# Sheet1.net
KiCad netlist of a schematic drawn in Altium Designer
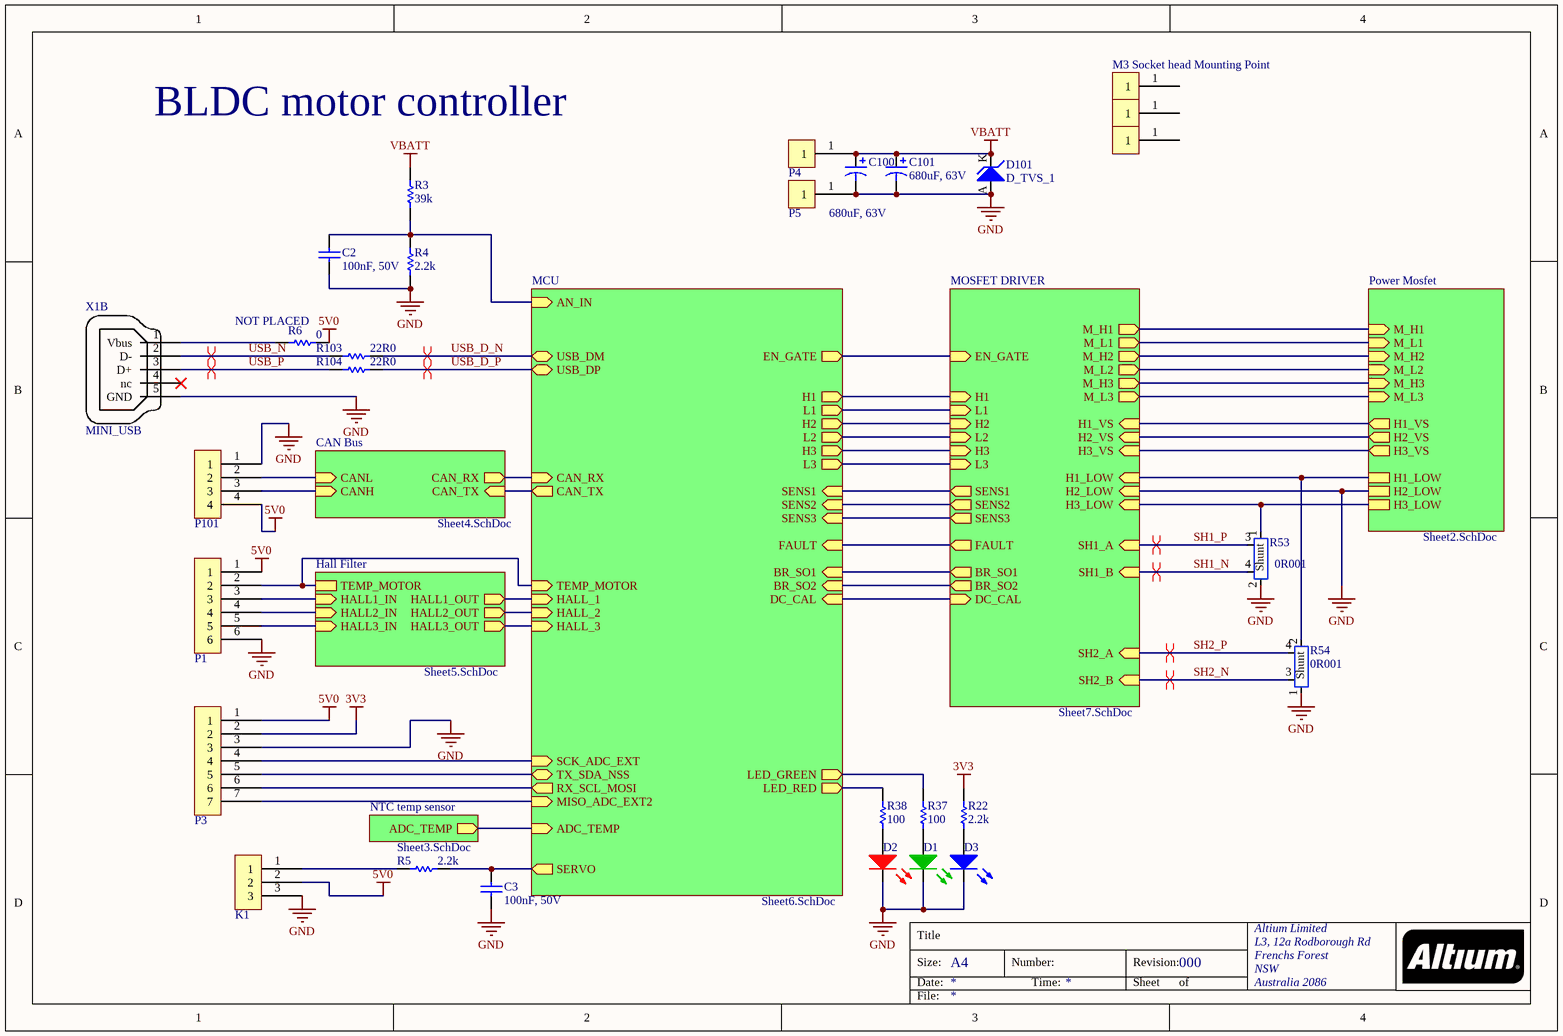
[diagram p0: Sheet1.SchDoc]

(export (version "E")
  (design (tool "Eeschema 10.0.6"))
  (components
    (comp (ref "C2")
      (value "100nF, 50V")
      (footprint "SMD-0603 Capacitor")
      (description "CAP 100n, 50V, 0603")
      (fields
        (field (name "MANUFACTURER PART NUMBER") "06035C104JAT2A")
        (field (name "MANUFACTURER") "AVX Corporation")
      )
      (libsource (lib "Master Data Link") (part "CAP"))
    )
    (comp (ref "C3")
      (value "100nF, 50V")
      (footprint "SMD-0603 Capacitor")
      (description "CAP 100n, 50V, 0603")
      (fields
        (field (name "MANUFACTURER PART NUMBER") "06035C104JAT2A")
        (field (name "MANUFACTURER") "AVX Corporation")
      )
      (libsource (lib "Master Data Link") (part "CAP"))
    )
    (comp (ref "C100")
      (value "680uF, 63V")
      (footprint "ALU CAP 16DIA 25HIGH")
      (description "680µF 63V Aluminum Capacitors Radial")
      (fields
        (field (name "MANUFACTURER PART NUMBER") "UPW1J681MHD")
        (field (name "MANUFACTURER") "Nichicon")
      )
      (libsource (lib "Master Data Link") (part "CAP_POL"))
    )
    (comp (ref "C101")
      (value "680uF, 63V")
      (footprint "ALU CAP 16DIA 25HIGH")
      (description "680µF 63V Aluminum Capacitors Radial")
      (fields
        (field (name "MANUFACTURER PART NUMBER") "UPW1J681MHD")
        (field (name "MANUFACTURER") "Nichicon")
      )
      (libsource (lib "Master Data Link") (part "CAP_POL"))
    )
    (comp (ref "D1")
      (value "LED_GREEN")
      (footprint "SMD-0603 LED GREEN")
      (description "LED Green, 0603")
      (fields (field (name "PART NUMBER") "LTST-C191KGKT") (field (name "MANUFACTURER") "Lite-On Inc."))
      (libsource (lib "Master Data Link") (part "LED_GREEN"))
    )
    (comp (ref "D2")
      (value "LED_RED")
      (footprint "SMD-0603 LED RED")
      (description "LED Red, 0603")
      (fields (field (name "PART NUMBER") "LTST-C191KRKT") (field (name "MANUFACTURER") "Lite-On Inc."))
      (libsource (lib "Master Data Link") (part "LED_RED"))
    )
    (comp (ref "D3")
      (value "LED_BLUE")
      (footprint "SMD-0603 LED BLUE")
      (description "LED Blue, 0603")
      (fields (field (name "PART NUMBER") "LBQ39GN1P1351") (field (name "MANUFACTURER") "OSRAM"))
      (libsource (lib "Master Data Link") (part "LED_BLUE"))
    )
    (comp (ref "D101")
      (value "D_TVS_1")
      (footprint "SMC-403-03")
      (description "TVS DIODE 51VWM 82.4VC SMC")
      (fields
        (field (name "MANUFACTURER PART NUMBER") "SMCJ51A")
        (field (name "MANUFACTURER") "ON Semiconductor")
      )
      (libsource (lib "Master Data Link") (part "D_TVS_1"))
    )
    (comp (ref "K1")
      (value "-")
      (footprint "HEADER 3 PIN")
      (description "Breakaway 3 pin Through hole")
      (libsource (lib "Master Data Link") (part "CON3"))
    )
    (comp (ref "M1")
      (value "M3 Socket head Mounting Point")
      (footprint "M3 Socket head")
      (libsource (lib "Master Data Link") (part "CON1"))
    )
    (comp (ref "M2")
      (value "M3 Socket head Mounting Point")
      (footprint "M3 Socket head")
      (libsource (lib "Master Data Link") (part "CON1"))
    )
    (comp (ref "M3")
      (value "M3 Socket head Mounting Point")
      (footprint "M3 Socket head")
      (libsource (lib "Master Data Link") (part "CON1"))
    )
    (comp (ref "P1")
      (value "B6B-PH-K-S(LF)(SN)")
      (footprint "JST PH TH VERT 6")
      (description "JST PH Through hole Vertical 6 Pin")
      (fields (field (name "MANUFACTURER") "JST"))
      (libsource (lib "Master Data Link") (part "CON6"))
    )
    (comp (ref "P3")
      (value "B7B-PH-K-S(LF)(SN)")
      (footprint "JST PH TH VERT 7")
      (description "JST PH Through hole Vertical 7 Pin")
      (fields (field (name "MANUFACTURER") "JST"))
      (libsource (lib "Master Data Link") (part "CON7"))
    )
    (comp (ref "P4")
      (value "-")
      (footprint "PAD1")
      (description "SMD Power landing")
      (libsource (lib "Master Data Link") (part "CON1"))
    )
    (comp (ref "P5")
      (value "-")
      (footprint "PAD1")
      (description "SMD Power landing")
      (libsource (lib "Master Data Link") (part "CON1"))
    )
    (comp (ref "P101")
      (value "B4B-PH-K-S(LF)(SN)")
      (footprint "JST PH TH VERT 4")
      (description "JST PH Through hole Vertical 4 Pin")
      (fields (field (name "MANUFACTURER") "JST"))
      (libsource (lib "Master Data Link") (part "CON4"))
    )
    (comp (ref "R3")
      (value "39k")
      (footprint "SMD-0603 Resistor")
      (description "R 39k, 0603")
      (fields
        (field (name "MANUFACTURER PART NUMBER") "ERJ-3EKF3902V")
        (field (name "MANUFACTURER") "Panasonic Electronic Components")
      )
      (libsource (lib "Master Data Link") (part "RES"))
    )
    (comp (ref "R4")
      (value "2.2k")
      (footprint "SMD-0603 Resistor")
      (description "R 2.2k, 0603")
      (fields
        (field (name "MANUFACTURER PART NUMBER") "RK73H1JTTD2201F")
        (field (name "MANUFACTURER") "KOA Speer")
      )
      (libsource (lib "Master Data Link") (part "RES"))
    )
    (comp (ref "R5")
      (value "2.2k")
      (footprint "SMD-0603 Resistor")
      (description "R 2.2k, 0603")
      (fields
        (field (name "MANUFACTURER PART NUMBER") "RK73H1JTTD2201F")
        (field (name "MANUFACTURER") "KOA Speer")
      )
      (libsource (lib "Master Data Link") (part "RES"))
    )
    (comp (ref "R6")
      (value "0")
      (footprint "SMD-0603 Resistor")
      (description "R 0 ohm, 0603")
      (fields (field (name "PLACE (YES/NO)") "NOT PLACED") (field (name "MANUFACTURER") "KOA Speer"))
      (libsource (lib "Master Data Link") (part "RES"))
    )
    (comp (ref "R22")
      (value "2.2k")
      (footprint "SMD-0603 Resistor")
      (description "R 2.2k, 0603")
      (fields
        (field (name "MANUFACTURER PART NUMBER") "RK73H1JTTD2201F")
        (field (name "MANUFACTURER") "KOA Speer")
      )
      (libsource (lib "Master Data Link") (part "RES"))
    )
    (comp (ref "R37")
      (value "100")
      (footprint "SMD-0603 Resistor")
      (description "R 100ohm, 0603")
      (fields
        (field (name "MANUFACTURER PART NUMBER") "RK73H1JTTD1000F")
        (field (name "MANUFACTURER") "KOA Speer")
      )
      (libsource (lib "Master Data Link") (part "RES"))
    )
    (comp (ref "R38")
      (value "100")
      (footprint "SMD-0603 Resistor")
      (description "R 100ohm, 0603")
      (fields
        (field (name "MANUFACTURER PART NUMBER") "RK73H1JTTD1000F")
        (field (name "MANUFACTURER") "KOA Speer")
      )
      (libsource (lib "Master Data Link") (part "RES"))
    )
    (comp (ref "R53")
      (value "0R001")
      (footprint "WSLP2726")
      (description "Shunt 1mOhm")
      (fields
        (field (name "MANUFACTURER PART NUMBER") "WSLP27261L000FEA")
        (field (name "MANUFACTURER") "Vishay Dale")
      )
      (libsource (lib "Master Data Link") (part "SHUNT_1"))
    )
    (comp (ref "R54")
      (value "0R001")
      (footprint "WSLP2726")
      (description "Shunt 1mOhm MIRROR")
      (fields
        (field (name "MANUFACTURER PART NUMBER") "WSLP27261L000FEA")
        (field (name "MANUFACTURER") "Vishay Dale")
      )
      (libsource (lib "Master Data Link") (part "SHUNT_2"))
    )
    (comp (ref "R103")
      (value "22R0")
      (footprint "SMD-0603 Resistor")
      (description "R 22R, 0603")
      (fields
        (field (name "MANUFACTURER PART NUMBER") "RK73H1JTTD22R0F")
        (field (name "MANUFACTURER") "KOA Speer")
      )
      (libsource (lib "Master Data Link") (part "RES"))
    )
    (comp (ref "R104")
      (value "22R0")
      (footprint "SMD-0603 Resistor")
      (description "R 22R, 0603")
      (fields
        (field (name "MANUFACTURER PART NUMBER") "RK73H1JTTD22R0F")
        (field (name "MANUFACTURER") "KOA Speer")
      )
      (libsource (lib "Master Data Link") (part "RES"))
    )
    (comp (ref "X1B")
      (value "MINI_USB")
      (footprint "USB-MICRO B RA SMT-TH")
      (description "CONN USB MICRO B RECPT SMT R/A TH")
      (fields
        (field (name "MANUFACTURER PART NUMBER") "10118194-0001LF")
        (field (name "MANUFACTURER") "Amphenol FCI")
      )
      (libsource (lib "Master Data Link") (part "MINI_USB"))
    )
  )
  (nets
    (net (code "2") (name "/AN_IN") (class "Default")
      (node (ref "C2") (pin "1") (pinfunction "1_1") (pintype "passive"))
      (node (ref "R3") (pin "1") (pinfunction "1_1") (pintype "passive"))
      (node (ref "R4") (pin "2") (pinfunction "2_2") (pintype "passive"))
    )
    (net (code "5") (name "/CANH") (class "Default")
      (node (ref "P101") (pin "3") (pinfunction "3_3") (pintype "passive"))
    )
    (net (code "6") (name "/CANL") (class "Default")
      (node (ref "P101") (pin "2") (pinfunction "2_2") (pintype "passive"))
    )
    (net (code "13") (name "/H1_LOW") (class "Default")
      (node (ref "R54") (pin "2") (pinfunction "1_2") (pintype "passive"))
    )
    (net (code "18") (name "/H3_LOW") (class "Default")
      (node (ref "R53") (pin "1") (pinfunction "1_1") (pintype "passive"))
    )
    (net (code "20") (name "/HALL1_IN") (class "Default")
      (node (ref "P1") (pin "3") (pinfunction "3_3") (pintype "passive"))
    )
    (net (code "22") (name "/HALL2_IN") (class "Default")
      (node (ref "P1") (pin "4") (pinfunction "4_4") (pintype "passive"))
    )
    (net (code "24") (name "/HALL3_IN") (class "Default")
      (node (ref "P1") (pin "5") (pinfunction "5_5") (pintype "passive"))
    )
    (net (code "29") (name "/LED_GREEN") (class "Default")
      (node (ref "R37") (pin "2") (pinfunction "2_2") (pintype "passive"))
    )
    (net (code "30") (name "/LED_RED") (class "Default")
      (node (ref "R38") (pin "2") (pinfunction "2_2") (pintype "passive"))
    )
    (net (code "31") (name "/MISO_ADC_EXT2") (class "Default")
      (node (ref "P3") (pin "7") (pinfunction "7_7") (pintype "passive"))
    )
    (net (code "38") (name "/RX_SCL_MOSI") (class "Default")
      (node (ref "P3") (pin "6") (pinfunction "6_6") (pintype "passive"))
    )
    (net (code "39") (name "/SCK_ADC_EXT") (class "Default")
      (node (ref "P3") (pin "4") (pinfunction "4_4") (pintype "passive"))
    )
    (net (code "43") (name "/SERVO") (class "Default")
      (node (ref "C3") (pin "2") (pinfunction "2_2") (pintype "passive"))
      (node (ref "R5") (pin "2") (pinfunction "2_2") (pintype "passive"))
    )
    (net (code "44") (name "/SH1_N") (class "Default")
      (node (ref "R53") (pin "4") (pinfunction "3_4") (pintype "passive"))
    )
    (net (code "45") (name "/SH1_P") (class "Default")
      (node (ref "R53") (pin "3") (pinfunction "2_3") (pintype "passive"))
    )
    (net (code "46") (name "/SH2_N") (class "Default")
      (node (ref "R54") (pin "3") (pinfunction "3_3") (pintype "passive"))
    )
    (net (code "47") (name "/SH2_P") (class "Default")
      (node (ref "R54") (pin "4") (pinfunction "2_4") (pintype "passive"))
    )
    (net (code "48") (name "/TEMP_MOTOR") (class "Default")
      (node (ref "P1") (pin "2") (pinfunction "2_2") (pintype "passive"))
    )
    (net (code "49") (name "/TX_SDA_NSS") (class "Default")
      (node (ref "P3") (pin "5") (pinfunction "5_5") (pintype "passive"))
    )
    (net (code "50") (name "/USB_D_N") (class "Default")
      (node (ref "R103") (pin "2") (pinfunction "2_2") (pintype "passive"))
    )
    (net (code "51") (name "/USB_D_P") (class "Default")
      (node (ref "R104") (pin "2") (pinfunction "2_2") (pintype "passive"))
    )
    (net (code "52") (name "/USB_N") (class "Default")
      (node (ref "R103") (pin "1") (pinfunction "1_1") (pintype "passive"))
      (node (ref "X1B") (pin "2") (pinfunction "D-_2") (pintype "passive"))
    )
    (net (code "53") (name "/USB_P") (class "Default")
      (node (ref "R104") (pin "1") (pinfunction "1_1") (pintype "passive"))
      (node (ref "X1B") (pin "3") (pinfunction "D+_3") (pintype "passive"))
    )
    (net (code "54") (name "3V3") (class "Default")
      (node (ref "P3") (pin "2") (pinfunction "2_2") (pintype "passive"))
      (node (ref "R22") (pin "2") (pinfunction "2_2") (pintype "passive"))
    )
    (net (code "55") (name "5V0") (class "Default")
      (node (ref "K1") (pin "2") (pinfunction "2_2") (pintype "passive"))
      (node (ref "P1") (pin "1") (pinfunction "1_1") (pintype "passive"))
      (node (ref "P101") (pin "4") (pinfunction "4_4") (pintype "passive"))
      (node (ref "P3") (pin "1") (pinfunction "1_1") (pintype "passive"))
      (node (ref "R6") (pin "2") (pinfunction "2_2") (pintype "passive"))
    )
    (net (code "56") (name "GND") (class "Default")
      (node (ref "C100") (pin "2") (pinfunction "2_2") (pintype "passive"))
      (node (ref "C101") (pin "2") (pinfunction "2_2") (pintype "passive"))
      (node (ref "C2") (pin "2") (pinfunction "2_2") (pintype "passive"))
      (node (ref "C3") (pin "1") (pinfunction "1_1") (pintype "passive"))
      (node (ref "D1") (pin "2") (pinfunction "2_2") (pintype "passive"))
      (node (ref "D101") (pin "A") (pinfunction "A_A") (pintype "passive"))
      (node (ref "D2") (pin "2") (pinfunction "2_2") (pintype "passive"))
      (node (ref "D3") (pin "2") (pinfunction "2_2") (pintype "passive"))
      (node (ref "K1") (pin "3") (pinfunction "3_3") (pintype "passive"))
      (node (ref "P1") (pin "6") (pinfunction "6_6") (pintype "passive"))
      (node (ref "P101") (pin "1") (pinfunction "1_1") (pintype "passive"))
      (node (ref "P3") (pin "3") (pinfunction "3_3") (pintype "passive"))
      (node (ref "P5") (pin "1") (pinfunction "1_1") (pintype "passive"))
      (node (ref "R4") (pin "1") (pinfunction "1_1") (pintype "passive"))
      (node (ref "R53") (pin "2") (pinfunction "2_2") (pintype "passive"))
      (node (ref "R54") (pin "1") (pinfunction "2_1") (pintype "passive"))
      (node (ref "X1B") (pin "5") (pinfunction "GND_5") (pintype "passive"))
    )
    (net (code "57") (name "Net-(D1-Pad1)") (class "Default")
      (node (ref "D1") (pin "1") (pinfunction "1_1") (pintype "passive"))
      (node (ref "R37") (pin "1") (pinfunction "1_1") (pintype "passive"))
    )
    (net (code "58") (name "Net-(D2-Pad1)") (class "Default")
      (node (ref "D2") (pin "1") (pinfunction "1_1") (pintype "passive"))
      (node (ref "R38") (pin "1") (pinfunction "1_1") (pintype "passive"))
    )
    (net (code "59") (name "Net-(D3-Pad1)") (class "Default")
      (node (ref "D3") (pin "1") (pinfunction "1_1") (pintype "passive"))
      (node (ref "R22") (pin "1") (pinfunction "1_1") (pintype "passive"))
    )
    (net (code "60") (name "Net-(K1-Pad1)") (class "Default")
      (node (ref "K1") (pin "1") (pinfunction "1_1") (pintype "passive"))
      (node (ref "R5") (pin "1") (pinfunction "1_1") (pintype "passive"))
    )
    (net (code "61") (name "Net-(X1B-Vbus)") (class "Default")
      (node (ref "R6") (pin "1") (pinfunction "1_1") (pintype "passive"))
      (node (ref "X1B") (pin "1") (pinfunction "Vbus_1") (pintype "passive"))
    )
    (net (code "62") (name "VBATT") (class "Default")
      (node (ref "C100") (pin "1") (pinfunction "1_1") (pintype "passive"))
      (node (ref "C101") (pin "1") (pinfunction "1_1") (pintype "passive"))
      (node (ref "D101") (pin "K") (pinfunction "K_K") (pintype "passive"))
      (node (ref "P4") (pin "1") (pinfunction "1_1") (pintype "passive"))
      (node (ref "R3") (pin "2") (pinfunction "2_2") (pintype "passive"))
    )
    (net (code "63") (name "unconnected-(M1-Pad1)") (class "Default")
      (node (ref "M1") (pin "1") (pinfunction "1_1") (pintype "passive"))
    )
    (net (code "64") (name "unconnected-(M2-Pad1)") (class "Default")
      (node (ref "M2") (pin "1") (pinfunction "1_1") (pintype "passive"))
    )
    (net (code "65") (name "unconnected-(M3-Pad1)") (class "Default")
      (node (ref "M3") (pin "1") (pinfunction "1_1") (pintype "passive"))
    )
    (net (code "66") (name "unconnected-(X1B-nc-Pad4)") (class "Default")
      (node (ref "X1B") (pin "4") (pinfunction "nc_4") (pintype "passive+no_connect"))
    )
  )
)
